# NTC_Thermistor_10K_Parallel_VDiv.net
KiCad netlist of a schematic drawn in Altium Designer
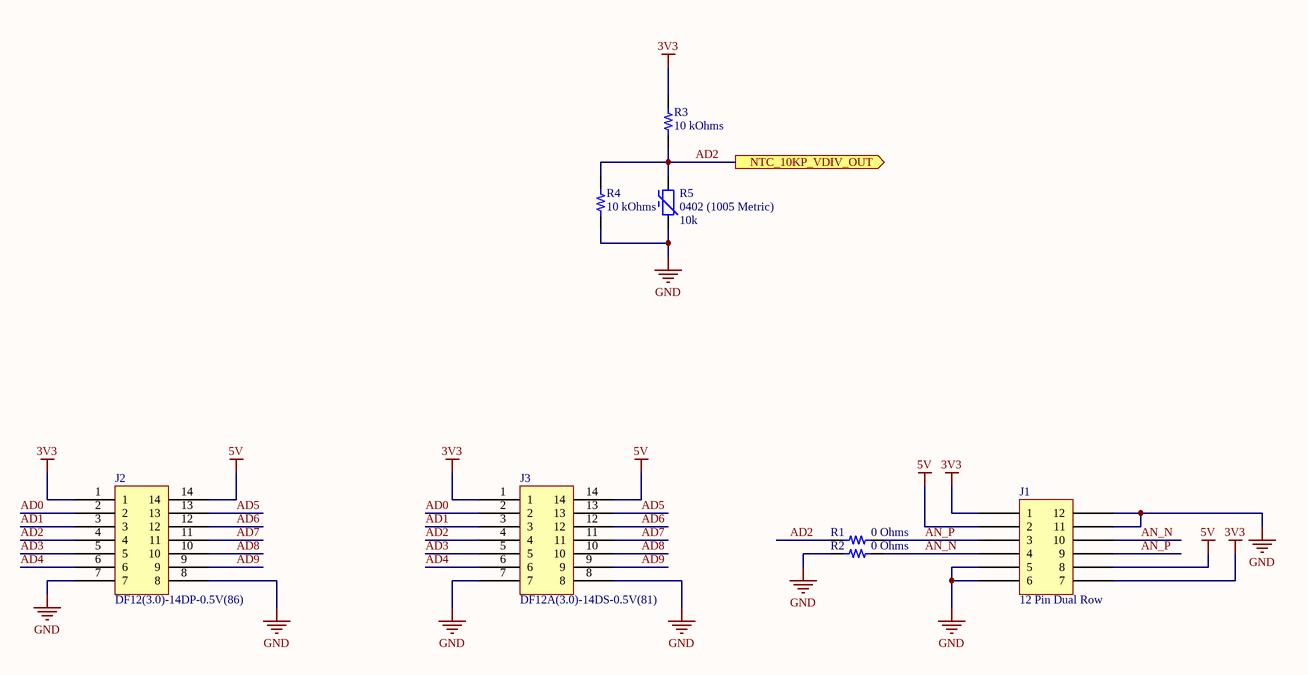
[diagram p0: NTC Thermistor 10K Parallel VDiv.SchDoc]

(export (version "E")
  (design (tool "Eeschema 10.0.6"))
  (components
    (comp (ref "J1")
      (value "12 Pin Dual Row")
      (footprint "TE 5650118-3 Card Edge")
      (libsource (lib "CelestialUseful") (part "12 Pin Dual Row"))
    )
    (comp (ref "J2")
      (value "DF12(3.0)-14DP-0.5V(86)")
      (footprint "HIROSE DF12 3.0-14DP-0.5V 86")
      (description "CONN HDR 14POS SMD GOLD")
      (fields (field (name "MANUFACTURER") "Hirose Electric Co Ltd"))
      (libsource (lib "altiumlibrary.com") (part "14 Pin Dual Row"))
    )
    (comp (ref "J3")
      (value "DF12A(3.0)-14DS-0.5V(81)")
      (footprint "HIROSE DF12A 3.0-14DS-0.5V 81")
      (description "CONN RCPT 14POS SMD GOLD")
      (fields (field (name "MANUFACTURER") "Hirose Electric Co Ltd"))
      (libsource (lib "altiumlibrary.com") (part "14 Pin Dual Row"))
    )
    (comp (ref "R1")
      (value "0 Ohms")
      (footprint "RES 0603_1608")
      (description "RES SMD 0 OHM JUMPER 1/10W 0603")
      (fields
        (field (name "PART NUMBER") "ERJ-3GEY0R00V")
        (field (name "MANUFACTURER") "Panasonic Electronic Components")
      )
      (libsource (lib "altiumlibrary.com") (part "Resistor"))
    )
    (comp (ref "R2")
      (value "0 Ohms")
      (footprint "RES 0603_1608")
      (description "RES SMD 0 OHM JUMPER 1/10W 0603")
      (fields
        (field (name "PART NUMBER") "ERJ-3GEY0R00V")
        (field (name "MANUFACTURER") "Panasonic Electronic Components")
      )
      (libsource (lib "altiumlibrary.com") (part "Resistor"))
    )
    (comp (ref "R3")
      (value "10 kOhms")
      (footprint "RES 0603_1608")
      (description "RES SMD 10K OHM 1% 1/10W 0603")
      (fields
        (field (name "PART NUMBER") "ERJ-3EKF1002V")
        (field (name "MANUFACTURER") "Panasonic Electronic Components")
      )
      (libsource (lib "altiumlibrary.com") (part "Resistor"))
    )
    (comp (ref "R4")
      (value "10 kOhms")
      (footprint "RES 0603_1608")
      (description "RES SMD 10K OHM 1% 1/10W 0603")
      (fields
        (field (name "PART NUMBER") "ERJ-3EKF1002V")
        (field (name "MANUFACTURER") "Panasonic Electronic Components")
      )
      (libsource (lib "altiumlibrary.com") (part "Resistor"))
    )
    (comp (ref "R5")
      (value "NCP15XH103F03RC")
      (footprint "NTC 0402_1005")
      (description "THERMISTOR NTC 10KOHM 3380K 0402")
      (fields
        (field (name "MANUFACTURER") "Murata Electronics")
        (field (name "PACKAGE / CASE") "0402 (1005 Metric)")
        (field (name "RESISTANCE IN OHMS @ 25°C") "10k")
      )
      (libsource (lib "altiumlibrary.com") (part "Thermistor"))
    )
  )
  (nets
    (net (code "1") (name "/AD0") (class "Default")
      (node (ref "J2") (pin "2") (pinfunction "2_2") (pintype "passive"))
      (node (ref "J3") (pin "2") (pinfunction "2_2") (pintype "passive"))
    )
    (net (code "2") (name "/AD1") (class "Default")
      (node (ref "J2") (pin "3") (pinfunction "3_3") (pintype "passive"))
      (node (ref "J3") (pin "3") (pinfunction "3_3") (pintype "passive"))
    )
    (net (code "3") (name "/AD2") (class "Default")
      (node (ref "J2") (pin "4") (pinfunction "4_4") (pintype "passive"))
      (node (ref "J3") (pin "4") (pinfunction "4_4") (pintype "passive"))
      (node (ref "R1") (pin "1") (pinfunction "1_1") (pintype "passive"))
      (node (ref "R3") (pin "1") (pinfunction "1_1") (pintype "passive"))
      (node (ref "R4") (pin "2") (pinfunction "2_2") (pintype "passive"))
      (node (ref "R5") (pin "1") (pinfunction "1_1") (pintype "passive"))
    )
    (net (code "4") (name "/AD3") (class "Default")
      (node (ref "J2") (pin "5") (pinfunction "5_5") (pintype "passive"))
      (node (ref "J3") (pin "5") (pinfunction "5_5") (pintype "passive"))
    )
    (net (code "5") (name "/AD4") (class "Default")
      (node (ref "J2") (pin "6") (pinfunction "6_6") (pintype "passive"))
      (node (ref "J3") (pin "6") (pinfunction "6_6") (pintype "passive"))
    )
    (net (code "6") (name "/AD5") (class "Default")
      (node (ref "J2") (pin "13") (pinfunction "13_13") (pintype "passive"))
      (node (ref "J3") (pin "13") (pinfunction "13_13") (pintype "passive"))
    )
    (net (code "7") (name "/AD6") (class "Default")
      (node (ref "J2") (pin "12") (pinfunction "12_12") (pintype "passive"))
      (node (ref "J3") (pin "12") (pinfunction "12_12") (pintype "passive"))
    )
    (net (code "8") (name "/AD7") (class "Default")
      (node (ref "J2") (pin "11") (pinfunction "11_11") (pintype "passive"))
      (node (ref "J3") (pin "11") (pinfunction "11_11") (pintype "passive"))
    )
    (net (code "9") (name "/AD8") (class "Default")
      (node (ref "J2") (pin "10") (pinfunction "10_10") (pintype "passive"))
      (node (ref "J3") (pin "10") (pinfunction "10_10") (pintype "passive"))
    )
    (net (code "10") (name "/AD9") (class "Default")
      (node (ref "J2") (pin "9") (pinfunction "9_9") (pintype "passive"))
      (node (ref "J3") (pin "9") (pinfunction "9_9") (pintype "passive"))
    )
    (net (code "11") (name "/AN_N") (class "Default")
      (node (ref "J1") (pin "10") (pinfunction "10_10") (pintype "passive"))
      (node (ref "J1") (pin "4") (pinfunction "4_4") (pintype "passive"))
      (node (ref "R2") (pin "2") (pinfunction "2_2") (pintype "passive"))
    )
    (net (code "12") (name "/AN_P") (class "Default")
      (node (ref "J1") (pin "3") (pinfunction "3_3") (pintype "passive"))
      (node (ref "J1") (pin "9") (pinfunction "9_9") (pintype "passive"))
      (node (ref "R1") (pin "2") (pinfunction "2_2") (pintype "passive"))
    )
    (net (code "13") (name "3V3") (class "Default")
      (node (ref "J1") (pin "1") (pinfunction "1_1") (pintype "passive"))
      (node (ref "J1") (pin "7") (pinfunction "7_7") (pintype "passive"))
      (node (ref "J2") (pin "1") (pinfunction "1_1") (pintype "passive"))
      (node (ref "J3") (pin "1") (pinfunction "1_1") (pintype "passive"))
      (node (ref "R3") (pin "2") (pinfunction "2_2") (pintype "passive"))
    )
    (net (code "14") (name "5V") (class "Default")
      (node (ref "J1") (pin "2") (pinfunction "2_2") (pintype "passive"))
      (node (ref "J1") (pin "8") (pinfunction "8_8") (pintype "passive"))
      (node (ref "J2") (pin "14") (pinfunction "14_14") (pintype "passive"))
      (node (ref "J3") (pin "14") (pinfunction "14_14") (pintype "passive"))
    )
    (net (code "15") (name "GND") (class "Default")
      (node (ref "J1") (pin "11") (pinfunction "11_11") (pintype "passive"))
      (node (ref "J1") (pin "12") (pinfunction "12_12") (pintype "passive"))
      (node (ref "J1") (pin "5") (pinfunction "5_5") (pintype "passive"))
      (node (ref "J1") (pin "6") (pinfunction "6_6") (pintype "passive"))
      (node (ref "J2") (pin "7") (pinfunction "7_7") (pintype "passive"))
      (node (ref "J2") (pin "8") (pinfunction "8_8") (pintype "passive"))
      (node (ref "J3") (pin "7") (pinfunction "7_7") (pintype "passive"))
      (node (ref "J3") (pin "8") (pinfunction "8_8") (pintype "passive"))
      (node (ref "R2") (pin "1") (pinfunction "1_1") (pintype "passive"))
      (node (ref "R4") (pin "1") (pinfunction "1_1") (pintype "passive"))
      (node (ref "R5") (pin "2") (pinfunction "2_2") (pintype "passive"))
    )
  )
)
